# VDMEDA_7SegDisp.net
KiCad netlist of a schematic drawn in Altium Designer
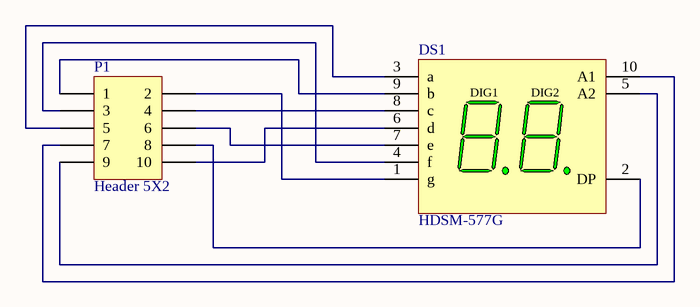
[diagram p0: VDMEDA_7SegDisp.SchDoc]

(export (version "E")
  (design (tool "Eeschema 10.0.6"))
  (components
    (comp (ref "DS1")
      (value "HDSM-577G")
      (footprint "HDSM-577")
      (description "9.2 mm Green 7-Segment Display: 2-Digit, RH DP")
      (fields (field (name "PUBLISHER") "Altium Limited"))
      (libsource (lib "Agilent LED Display 7-Segment, 2-Digit") (part "HDSM-577G"))
    )
    (comp (ref "P1")
      (value "Header 5X2")
      (footprint "HDR2X5")
      (description "Header, 5-Pin, Dual row")
      (fields (field (name "PUBLISHER") "Altium Limited"))
      (libsource (lib "Miscellaneous Connectors") (part "Header 5X2"))
    )
  )
  (nets
    (net (code "1") (name "Net-(DS1-A1)") (class "Default")
      (node (ref "DS1") (pin "10") (pinfunction "A1_10") (pintype "passive"))
      (node (ref "P1") (pin "7") (pinfunction "7_7") (pintype "passive"))
    )
    (net (code "2") (name "Net-(DS1-A2)") (class "Default")
      (node (ref "DS1") (pin "5") (pinfunction "A2_5") (pintype "passive"))
      (node (ref "P1") (pin "9") (pinfunction "9_9") (pintype "passive"))
    )
    (net (code "3") (name "Net-(DS1-DP)") (class "Default")
      (node (ref "DS1") (pin "2") (pinfunction "DP_2") (pintype "passive"))
      (node (ref "P1") (pin "8") (pinfunction "8_8") (pintype "passive"))
    )
    (net (code "4") (name "Net-(DS1-a)") (class "Default")
      (node (ref "DS1") (pin "3") (pinfunction "a_3") (pintype "passive"))
      (node (ref "P1") (pin "5") (pinfunction "5_5") (pintype "passive"))
    )
    (net (code "5") (name "Net-(DS1-b)") (class "Default")
      (node (ref "DS1") (pin "9") (pinfunction "b_9") (pintype "passive"))
      (node (ref "P1") (pin "1") (pinfunction "1_1") (pintype "passive"))
    )
    (net (code "6") (name "Net-(DS1-c)") (class "Default")
      (node (ref "DS1") (pin "8") (pinfunction "c_8") (pintype "passive"))
      (node (ref "P1") (pin "4") (pinfunction "4_4") (pintype "passive"))
    )
    (net (code "7") (name "Net-(DS1-d)") (class "Default")
      (node (ref "DS1") (pin "6") (pinfunction "d_6") (pintype "passive"))
      (node (ref "P1") (pin "10") (pinfunction "10_10") (pintype "passive"))
    )
    (net (code "8") (name "Net-(DS1-e)") (class "Default")
      (node (ref "DS1") (pin "7") (pinfunction "e_7") (pintype "passive"))
      (node (ref "P1") (pin "6") (pinfunction "6_6") (pintype "passive"))
    )
    (net (code "9") (name "Net-(DS1-f)") (class "Default")
      (node (ref "DS1") (pin "4") (pinfunction "f_4") (pintype "passive"))
      (node (ref "P1") (pin "3") (pinfunction "3_3") (pintype "passive"))
    )
    (net (code "10") (name "Net-(DS1-g)") (class "Default")
      (node (ref "DS1") (pin "1") (pinfunction "g_1") (pintype "passive"))
      (node (ref "P1") (pin "2") (pinfunction "2_2") (pintype "passive"))
    )
  )
)
